# mtr.net
KiCad netlist of a schematic drawn in EAGLE
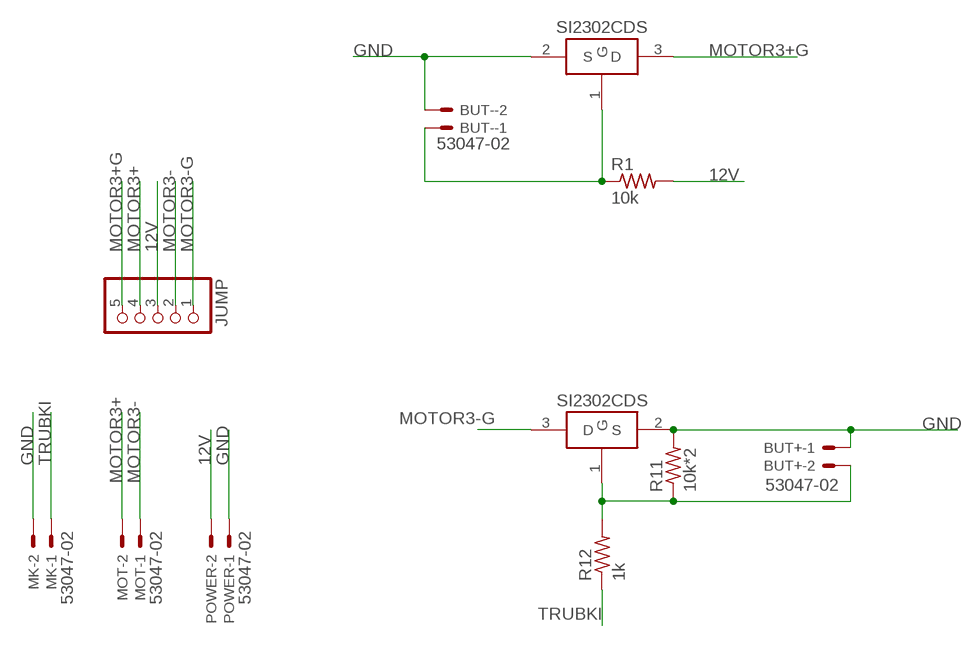
[diagram p0: schematic, sheet 1]

(export (version "E")
  (design (tool "Eeschema 10.0.6"))
  (components
    (comp (ref "BUT+")
      (value "53047-02")
      (footprint "eagle-import:53047-02")
      (fields (field (name "MF") "MOLEX") (field (name "MPN") "53047-0210"))
      (libsource (lib "eagle-import") (part "53?-02047"))
    )
    (comp (ref "BUT-")
      (value "53047-02")
      (footprint "eagle-import:53047-02")
      (fields (field (name "MF") "MOLEX") (field (name "MPN") "53047-0210"))
      (libsource (lib "eagle-import") (part "53?-02047"))
    )
    (comp (ref "JUMP")
      (value "PINHD-1X5")
      (footprint "eagle-import:1X05")
      (libsource (lib "eagle-import") (part "PINHD-1X5"))
    )
    (comp (ref "MK")
      (value "53047-02")
      (footprint "eagle-import:53047-02")
      (fields (field (name "MF") "MOLEX") (field (name "MPN") "53047-0210"))
      (libsource (lib "eagle-import") (part "53?-02047"))
    )
    (comp (ref "MOT")
      (value "53047-02")
      (footprint "eagle-import:53047-02")
      (fields (field (name "MF") "MOLEX") (field (name "MPN") "53047-0210"))
      (libsource (lib "eagle-import") (part "53?-02047"))
    )
    (comp (ref "POWER")
      (value "53047-02")
      (footprint "eagle-import:53047-02")
      (fields (field (name "MF") "MOLEX") (field (name "MPN") "53047-0210"))
      (libsource (lib "eagle-import") (part "53?-02047"))
    )
    (comp (ref "R1")
      (value "10k")
      (footprint "eagle-import:R0603")
      (libsource (lib "eagle-import") (part "R-US_R0603"))
    )
    (comp (ref "R11")
      (value "10k*2")
      (footprint "eagle-import:R0603")
      (libsource (lib "eagle-import") (part "R-US_R0603"))
    )
    (comp (ref "R12")
      (value "1k")
      (footprint "eagle-import:R0603")
      (libsource (lib "eagle-import") (part "R-US_R0603"))
    )
    (comp (ref "U$1")
      (value "SI2302CDS")
      (footprint "eagle-import:SOT23-3")
      (libsource (lib "eagle-import") (part "SI2302CDS"))
    )
    (comp (ref "U$21")
      (value "SI2302CDS")
      (footprint "eagle-import:SOT23-3")
      (libsource (lib "eagle-import") (part "SI2302CDS"))
    )
  )
  (nets
    (net (code "1") (name "/12V") (class "Default")
      (node (ref "JUMP") (pin "3") (pinfunction "3_3") (pintype "passive"))
      (node (ref "POWER") (pin "2") (pinfunction "S_2") (pintype "passive"))
      (node (ref "R1") (pin "2") (pinfunction "2_2") (pintype "passive"))
    )
    (net (code "2") (name "/GND") (class "Default")
      (node (ref "BUT+") (pin "1") (pinfunction "S_1") (pintype "passive"))
      (node (ref "BUT-") (pin "2") (pinfunction "S_2") (pintype "passive"))
      (node (ref "MK") (pin "2") (pinfunction "S_2") (pintype "passive"))
      (node (ref "POWER") (pin "1") (pinfunction "S_1") (pintype "passive"))
      (node (ref "R11") (pin "2") (pinfunction "2_2") (pintype "passive"))
      (node (ref "U$1") (pin "2") (pinfunction "S_2") (pintype "bidirectional"))
      (node (ref "U$21") (pin "2") (pinfunction "S_2") (pintype "bidirectional"))
    )
    (net (code "3") (name "/MOTOR3+") (class "Default")
      (node (ref "JUMP") (pin "4") (pinfunction "4_4") (pintype "passive"))
      (node (ref "MOT") (pin "2") (pinfunction "S_2") (pintype "passive"))
    )
    (net (code "4") (name "/MOTOR3+G") (class "Default")
      (node (ref "JUMP") (pin "5") (pinfunction "5_5") (pintype "passive"))
      (node (ref "U$21") (pin "3") (pinfunction "D_3") (pintype "bidirectional"))
    )
    (net (code "5") (name "/MOTOR3-") (class "Default")
      (node (ref "JUMP") (pin "2") (pinfunction "2_2") (pintype "passive"))
      (node (ref "MOT") (pin "1") (pinfunction "S_1") (pintype "passive"))
    )
    (net (code "6") (name "/MOTOR3-G") (class "Default")
      (node (ref "JUMP") (pin "1") (pinfunction "1_1") (pintype "passive"))
      (node (ref "U$1") (pin "3") (pinfunction "D_3") (pintype "bidirectional"))
    )
    (net (code "7") (name "/TRUBKI") (class "Default")
      (node (ref "MK") (pin "1") (pinfunction "S_1") (pintype "passive"))
      (node (ref "R12") (pin "1") (pinfunction "1_1") (pintype "passive"))
    )
    (net (code "8") (name "Net-(BUT+B-S)") (class "Default")
      (node (ref "BUT+") (pin "2") (pinfunction "S_2") (pintype "passive"))
      (node (ref "R11") (pin "1") (pinfunction "1_1") (pintype "passive"))
      (node (ref "R12") (pin "2") (pinfunction "2_2") (pintype "passive"))
      (node (ref "U$1") (pin "1") (pinfunction "G_1") (pintype "bidirectional"))
    )
    (net (code "9") (name "Net-(BUT-A-S)") (class "Default")
      (node (ref "BUT-") (pin "1") (pinfunction "S_1") (pintype "passive"))
      (node (ref "R1") (pin "1") (pinfunction "1_1") (pintype "passive"))
      (node (ref "U$21") (pin "1") (pinfunction "G_1") (pintype "bidirectional"))
    )
  )
)
